# sous-vide-panel.net
KiCad netlist of a schematic drawn in EAGLE
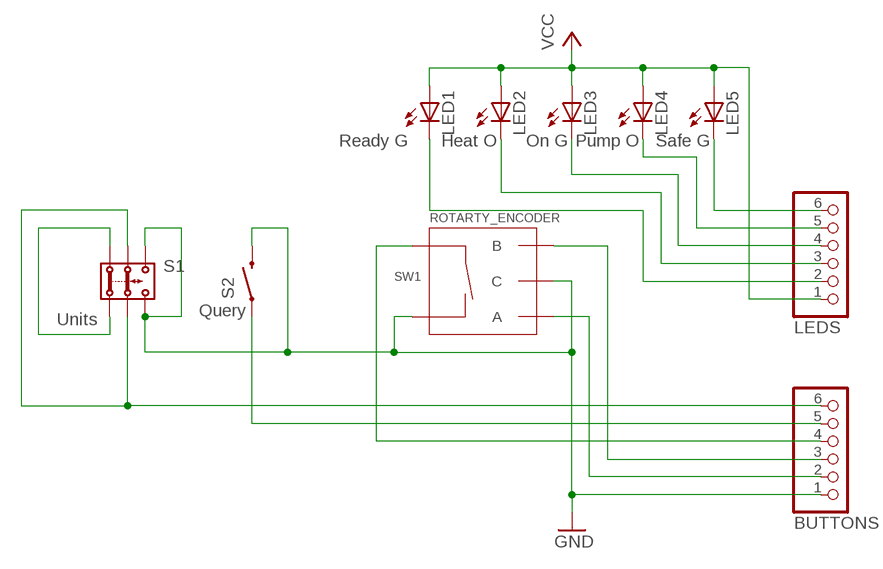
[diagram p0: schematic, sheet 1]

(export (version "E")
  (design (tool "Eeschema 10.0.6"))
  (components
    (comp (ref "BUTTONS")
      (value "PINHD-1X6")
      (footprint "eagle-import:1X06")
      (libsource (lib "eagle-import") (part "PINHD-1X6"))
    )
    (comp (ref "LED1")
      (value "Ready G")
      (footprint "eagle-import:LED5MM")
      (libsource (lib "eagle-import") (part "LED5MM"))
    )
    (comp (ref "LED2")
      (value "Heat O")
      (footprint "eagle-import:LED5MM")
      (libsource (lib "eagle-import") (part "LED5MM"))
    )
    (comp (ref "LED3")
      (value "On G")
      (footprint "eagle-import:LED5MM")
      (libsource (lib "eagle-import") (part "LED5MM"))
    )
    (comp (ref "LED4")
      (value "Pump O")
      (footprint "eagle-import:LED5MM")
      (libsource (lib "eagle-import") (part "LED5MM"))
    )
    (comp (ref "LED5")
      (value "Safe G")
      (footprint "eagle-import:LED5MM")
      (libsource (lib "eagle-import") (part "LED5MM"))
    )
    (comp (ref "LEDS")
      (value "PINHD-1X6")
      (footprint "eagle-import:1X06")
      (libsource (lib "eagle-import") (part "PINHD-1X6"))
    )
    (comp (ref "S1")
      (value "Units")
      (footprint "eagle-import:2P2T")
      (libsource (lib "eagle-import") (part "2P2T"))
    )
    (comp (ref "S2")
      (value "Query")
      (footprint "eagle-import:TACTILE-PTH-12MM")
      (libsource (lib "eagle-import") (part "SWITCH-MOMENTARY-212MM"))
    )
    (comp (ref "SW1")
      (value "ROTARTY_ENCODER")
      (footprint "eagle-import:ROTARY_ENC_PLAIN")
      (libsource (lib "eagle-import") (part "ROTARTY_ENCODER"))
    )
  )
  (nets
    (net (code "1") (name "GND") (class "Default")
      (node (ref "BUTTONS") (pin "1") (pinfunction "1_1") (pintype "passive"))
      (node (ref "S1") (pin "3.1") (pinfunction "3.1_3.1") (pintype "passive"))
      (node (ref "S1") (pin "3.2") (pinfunction "3.2_3.2") (pintype "passive"))
      (node (ref "S2") (pin "3") (pinfunction "2_3") (pintype "passive"))
      (node (ref "SW1") (pin "C") (pinfunction "C_C") (pintype "bidirectional"))
      (node (ref "SW1") (pin "SW-") (pinfunction "SW-_SW-") (pintype "bidirectional"))
    )
    (net (code "2") (name "Net-(BUTTONS-Pad2)") (class "Default")
      (node (ref "BUTTONS") (pin "2") (pinfunction "2_2") (pintype "passive"))
      (node (ref "SW1") (pin "A") (pinfunction "A_A") (pintype "bidirectional"))
    )
    (net (code "3") (name "Net-(BUTTONS-Pad3)") (class "Default")
      (node (ref "BUTTONS") (pin "3") (pinfunction "3_3") (pintype "passive"))
      (node (ref "SW1") (pin "B") (pinfunction "B_B") (pintype "bidirectional"))
    )
    (net (code "4") (name "Net-(BUTTONS-Pad4)") (class "Default")
      (node (ref "BUTTONS") (pin "4") (pinfunction "4_4") (pintype "passive"))
      (node (ref "SW1") (pin "SW+") (pinfunction "SW+_SW+") (pintype "bidirectional"))
    )
    (net (code "5") (name "Net-(BUTTONS-Pad5)") (class "Default")
      (node (ref "BUTTONS") (pin "5") (pinfunction "5_5") (pintype "passive"))
      (node (ref "S2") (pin "1") (pinfunction "1_1") (pintype "passive"))
    )
    (net (code "6") (name "Net-(BUTTONS-Pad6)") (class "Default")
      (node (ref "BUTTONS") (pin "6") (pinfunction "6_6") (pintype "passive"))
      (node (ref "S1") (pin "2.1") (pinfunction "2.1_2.1") (pintype "passive"))
      (node (ref "S1") (pin "2.2") (pinfunction "2.2_2.2") (pintype "passive"))
    )
    (net (code "7") (name "Net-(LED1-C)") (class "Default")
      (node (ref "LED1") (pin "K") (pinfunction "C_K") (pintype "passive"))
      (node (ref "LEDS") (pin "2") (pinfunction "2_2") (pintype "passive"))
    )
    (net (code "8") (name "Net-(LED2-C)") (class "Default")
      (node (ref "LED2") (pin "K") (pinfunction "C_K") (pintype "passive"))
      (node (ref "LEDS") (pin "3") (pinfunction "3_3") (pintype "passive"))
    )
    (net (code "9") (name "Net-(LED3-C)") (class "Default")
      (node (ref "LED3") (pin "K") (pinfunction "C_K") (pintype "passive"))
      (node (ref "LEDS") (pin "4") (pinfunction "4_4") (pintype "passive"))
    )
    (net (code "10") (name "Net-(LED4-C)") (class "Default")
      (node (ref "LED4") (pin "K") (pinfunction "C_K") (pintype "passive"))
      (node (ref "LEDS") (pin "5") (pinfunction "5_5") (pintype "passive"))
    )
    (net (code "11") (name "Net-(LED5-C)") (class "Default")
      (node (ref "LED5") (pin "K") (pinfunction "C_K") (pintype "passive"))
      (node (ref "LEDS") (pin "6") (pinfunction "6_6") (pintype "passive"))
    )
    (net (code "12") (name "Net-(S1-Pad1.1)") (class "Default")
      (node (ref "S1") (pin "1.1") (pinfunction "1.1_1.1") (pintype "passive"))
      (node (ref "S1") (pin "1.2") (pinfunction "1.2_1.2") (pintype "passive"))
    )
    (net (code "13") (name "VCC") (class "Default")
      (node (ref "LED1") (pin "A") (pinfunction "A_A") (pintype "passive"))
      (node (ref "LED2") (pin "A") (pinfunction "A_A") (pintype "passive"))
      (node (ref "LED3") (pin "A") (pinfunction "A_A") (pintype "passive"))
      (node (ref "LED4") (pin "A") (pinfunction "A_A") (pintype "passive"))
      (node (ref "LED5") (pin "A") (pinfunction "A_A") (pintype "passive"))
      (node (ref "LEDS") (pin "1") (pinfunction "1_1") (pintype "passive"))
    )
  )
)
